# 11-Stimulation.net
KiCad netlist of a schematic drawn in Altium Designer
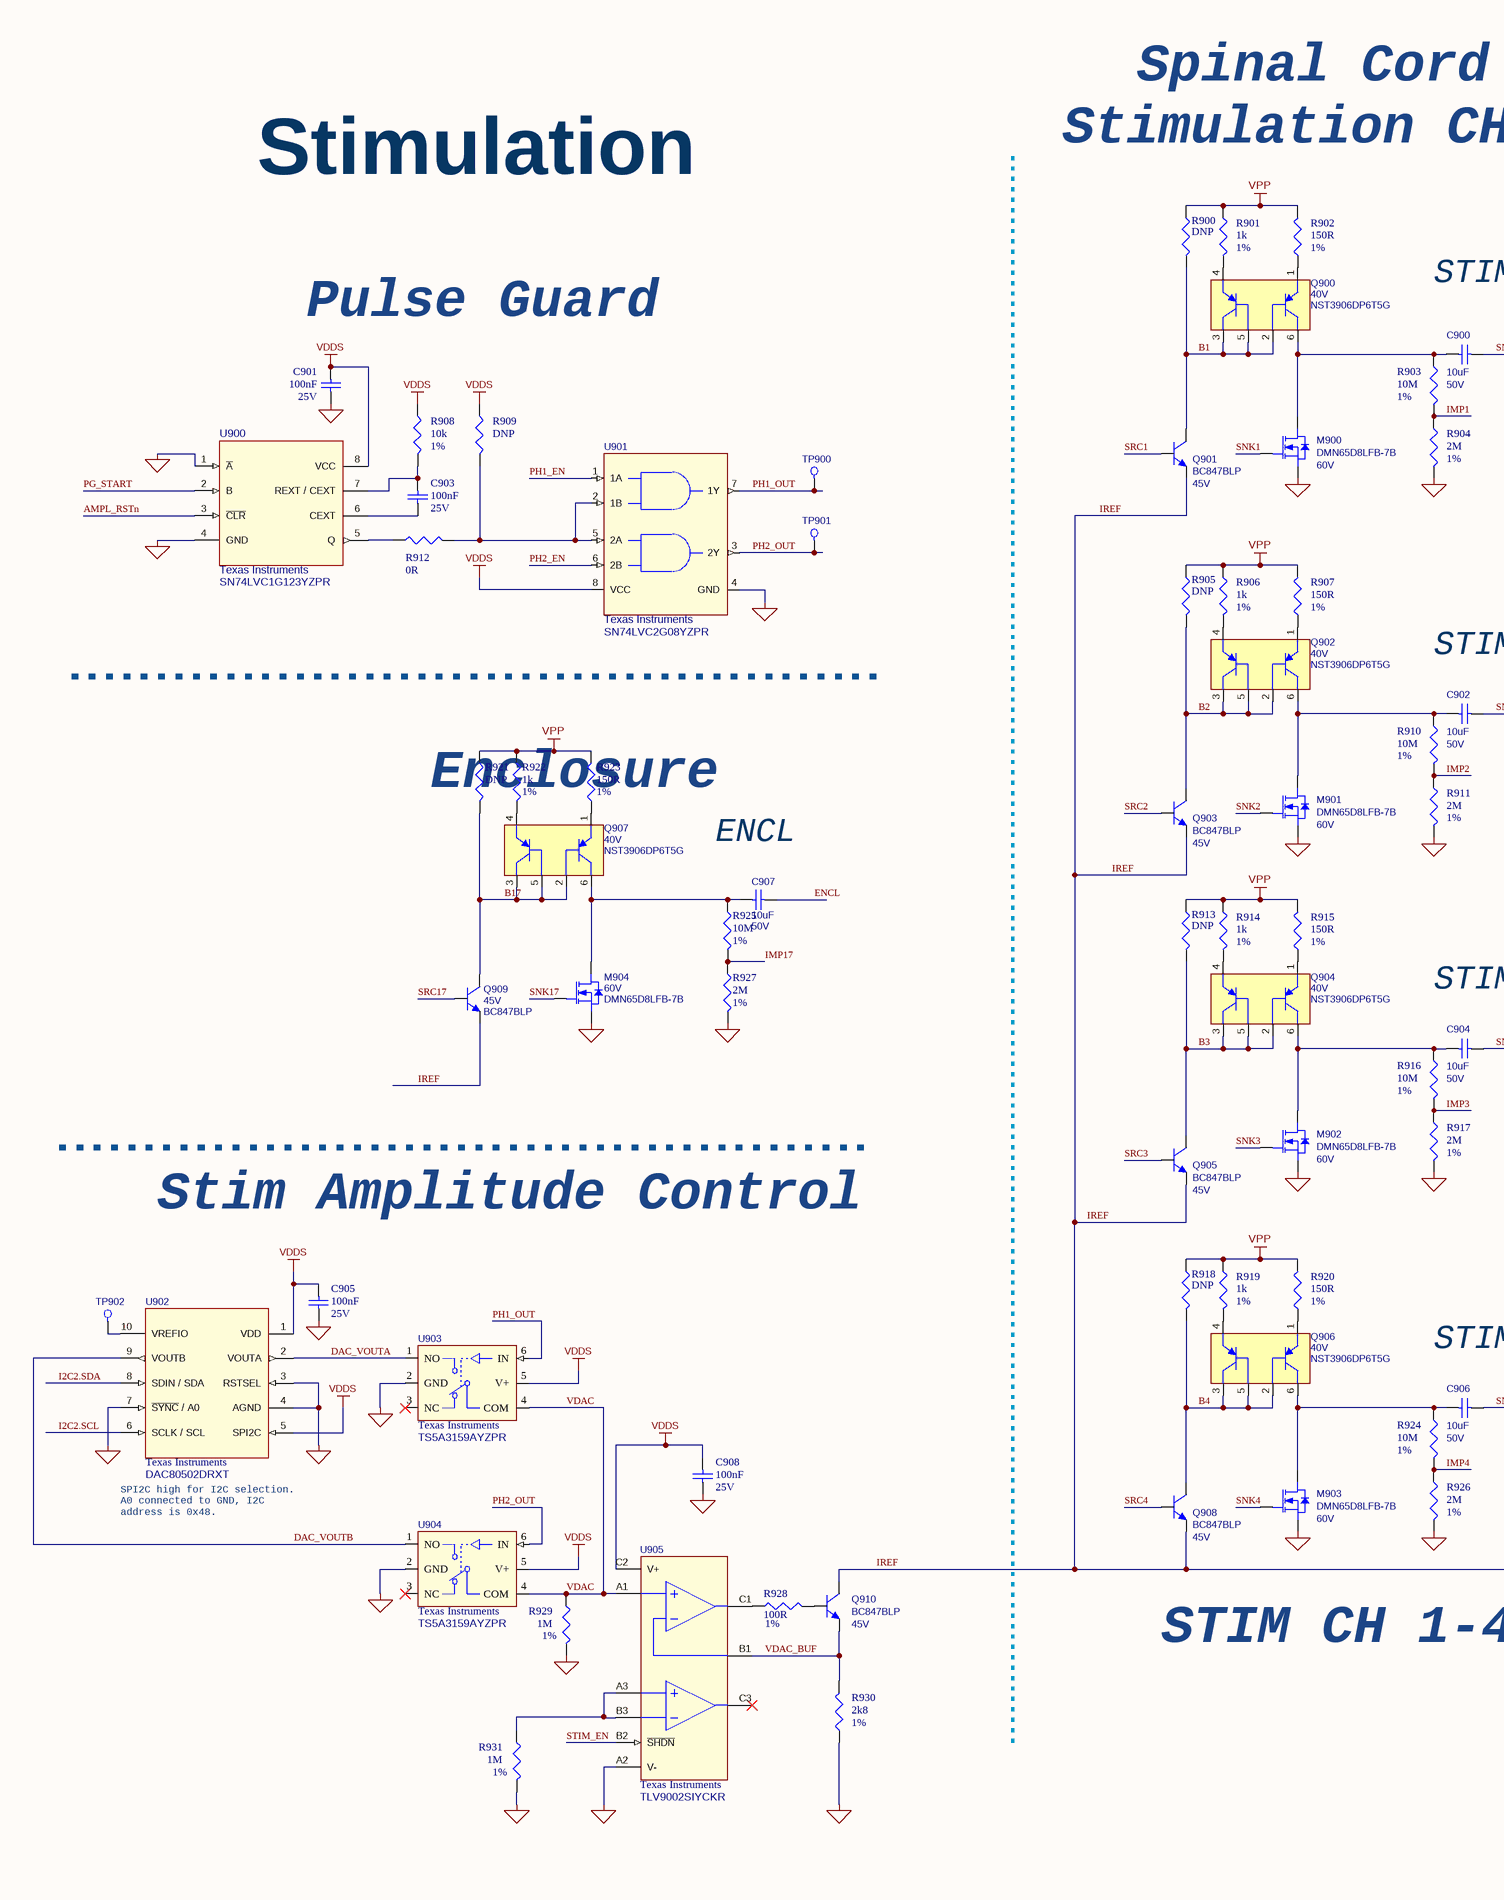
[diagram p0: 11-Stimulation.SchDoc, left]
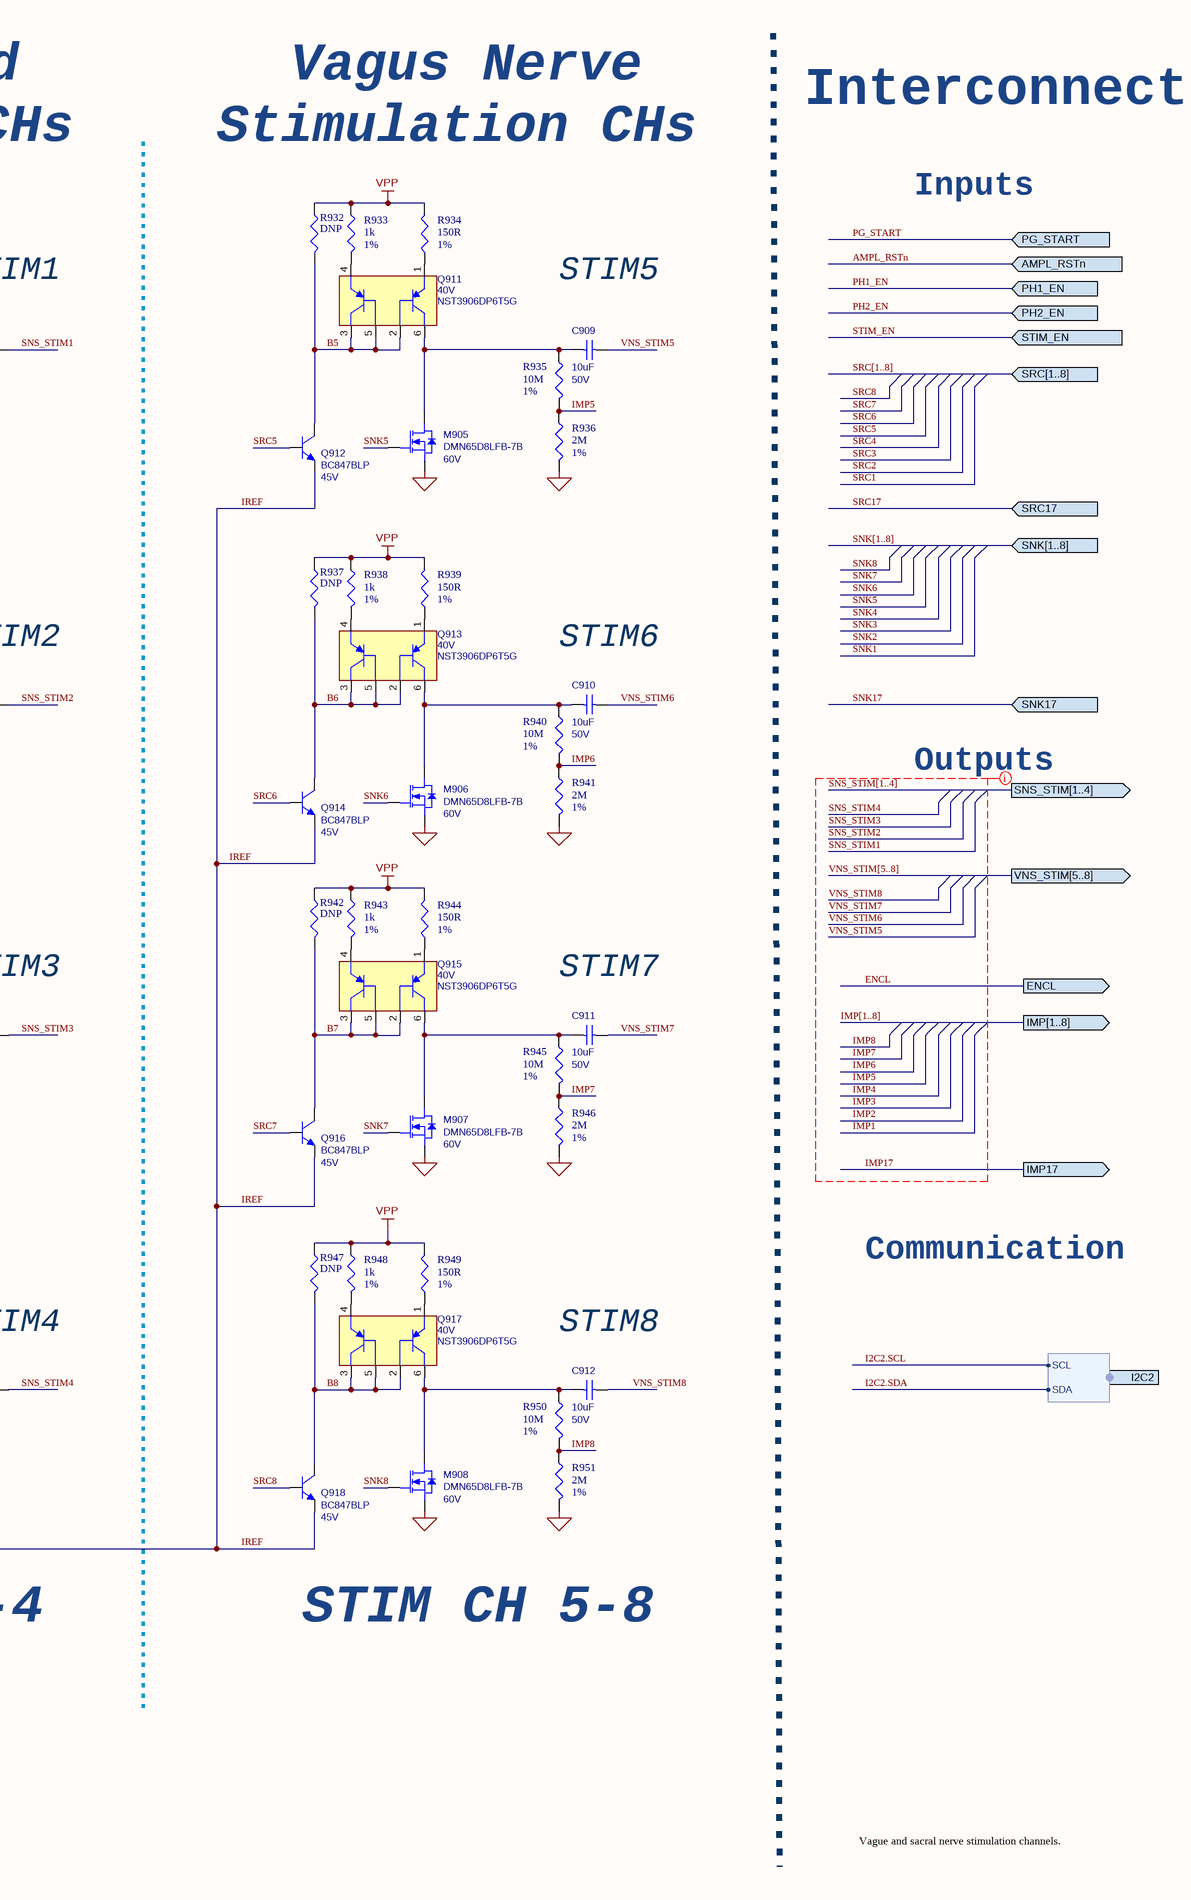
[diagram p1: 11-Stimulation.SchDoc, right]

(export (version "E")
  (design (tool "Eeschema 10.0.6"))
  (components
    (comp (ref "C900")
      (value "10uF")
      (footprint "CAP0805_REDUCED")
      (description "Capacitor, 10uF, X5R, 50V, 10%, 0805")
      (fields
        (field (name "MANUFACTURER") "Murata")
        (field (name "RATING") "50V")
        (field (name "MANUFACTURER PART NUMBER") "GRM21BR61H106ME43L")
      )
      (libsource (lib "MP-LIBRARY") (part "GRM21BR61H106ME43L"))
    )
    (comp (ref "C901")
      (value "100nF")
      (footprint "C0201_C")
      (fields
        (field (name "MANUFACTURER") "Murata")
        (field (name "MANUFACTURER PART NUMBER") "GRM033R61E104KE14J")
        (field (name "RATED DC VOLTAGE (URDC)") "25V")
      )
      (libsource (lib "MP-LIBRARY") (part "GRM033R61E104KE14J"))
    )
    (comp (ref "C902")
      (value "10uF")
      (footprint "CAP0805_REDUCED")
      (description "Capacitor, 10uF, X5R, 50V, 10%, 0805")
      (fields
        (field (name "MANUFACTURER") "Murata")
        (field (name "RATING") "50V")
        (field (name "MANUFACTURER PART NUMBER") "GRM21BR61H106ME43L")
      )
      (libsource (lib "MP-LIBRARY") (part "GRM21BR61H106ME43L"))
    )
    (comp (ref "C903")
      (value "100nF")
      (footprint "C0201_C")
      (fields
        (field (name "MANUFACTURER") "Murata")
        (field (name "MANUFACTURER PART NUMBER") "GRM033R61E104KE14J")
        (field (name "RATED DC VOLTAGE (URDC)") "25V")
      )
      (libsource (lib "MP-LIBRARY") (part "GRM033R61E104KE14J"))
    )
    (comp (ref "C904")
      (value "10uF")
      (footprint "CAP0805_REDUCED")
      (description "Capacitor, 10uF, X5R, 50V, 10%, 0805")
      (fields
        (field (name "MANUFACTURER") "Murata")
        (field (name "RATING") "50V")
        (field (name "MANUFACTURER PART NUMBER") "GRM21BR61H106ME43L")
      )
      (libsource (lib "MP-LIBRARY") (part "GRM21BR61H106ME43L"))
    )
    (comp (ref "C905")
      (value "100nF")
      (footprint "C0201_C")
      (fields
        (field (name "MANUFACTURER") "Murata")
        (field (name "MANUFACTURER PART NUMBER") "GRM033R61E104KE14J")
        (field (name "RATED DC VOLTAGE (URDC)") "25V")
      )
      (libsource (lib "MP-LIBRARY") (part "GRM033R61E104KE14J"))
    )
    (comp (ref "C906")
      (value "10uF")
      (footprint "CAP0805_REDUCED")
      (description "Capacitor, 10uF, X5R, 50V, 10%, 0805")
      (fields
        (field (name "MANUFACTURER") "Murata")
        (field (name "RATING") "50V")
        (field (name "MANUFACTURER PART NUMBER") "GRM21BR61H106ME43L")
      )
      (libsource (lib "MP-LIBRARY") (part "GRM21BR61H106ME43L"))
    )
    (comp (ref "C907")
      (value "10uF")
      (footprint "CAP0805_REDUCED")
      (description "Capacitor, 10uF, X5R, 50V, 10%, 0805")
      (fields
        (field (name "MANUFACTURER") "Murata")
        (field (name "RATING") "50V")
        (field (name "MANUFACTURER PART NUMBER") "GRM21BR61H106ME43L")
      )
      (libsource (lib "MP-LIBRARY") (part "GRM21BR61H106ME43L"))
    )
    (comp (ref "C908")
      (value "100nF")
      (footprint "C0201_C")
      (fields
        (field (name "MANUFACTURER") "Murata")
        (field (name "MANUFACTURER PART NUMBER") "GRM033R61E104KE14J")
        (field (name "RATED DC VOLTAGE (URDC)") "25V")
      )
      (libsource (lib "MP-LIBRARY") (part "GRM033R61E104KE14J"))
    )
    (comp (ref "C909")
      (value "10uF")
      (footprint "CAP0805_REDUCED")
      (description "Capacitor, 10uF, X5R, 50V, 10%, 0805")
      (fields
        (field (name "MANUFACTURER") "Murata")
        (field (name "RATING") "50V")
        (field (name "MANUFACTURER PART NUMBER") "GRM21BR61H106ME43L")
      )
      (libsource (lib "MP-LIBRARY") (part "GRM21BR61H106ME43L"))
    )
    (comp (ref "C910")
      (value "10uF")
      (footprint "CAP0805_REDUCED")
      (description "Capacitor, 10uF, X5R, 50V, 10%, 0805")
      (fields
        (field (name "MANUFACTURER") "Murata")
        (field (name "RATING") "50V")
        (field (name "MANUFACTURER PART NUMBER") "GRM21BR61H106ME43L")
      )
      (libsource (lib "MP-LIBRARY") (part "GRM21BR61H106ME43L"))
    )
    (comp (ref "C911")
      (value "10uF")
      (footprint "CAP0805_REDUCED")
      (description "Capacitor, 10uF, X5R, 50V, 10%, 0805")
      (fields
        (field (name "MANUFACTURER") "Murata")
        (field (name "RATING") "50V")
        (field (name "MANUFACTURER PART NUMBER") "GRM21BR61H106ME43L")
      )
      (libsource (lib "MP-LIBRARY") (part "GRM21BR61H106ME43L"))
    )
    (comp (ref "C912")
      (value "10uF")
      (footprint "CAP0805_REDUCED")
      (description "Capacitor, 10uF, X5R, 50V, 10%, 0805")
      (fields
        (field (name "MANUFACTURER") "Murata")
        (field (name "RATING") "50V")
        (field (name "MANUFACTURER PART NUMBER") "GRM21BR61H106ME43L")
      )
      (libsource (lib "MP-LIBRARY") (part "GRM21BR61H106ME43L"))
    )
    (comp (ref "M900")
      (value "DMN65D8LFB-7B")
      (footprint "DIODESINC_X1-DFN1006-3")
      (description "MOSFET, N-Chan, 60V, 210mA, DFN1006")
      (fields (field (name "MANUFACTURER") "Diodes Inc") (field (name "RATING") "60V"))
      (libsource (lib "MP-LIBRARY") (part "DMN65D8LFB-7B"))
    )
    (comp (ref "M901")
      (value "DMN65D8LFB-7B")
      (footprint "DIODESINC_X1-DFN1006-3")
      (description "MOSFET, N-Chan, 60V, 210mA, DFN1006")
      (fields (field (name "MANUFACTURER") "Diodes Inc") (field (name "RATING") "60V"))
      (libsource (lib "MP-LIBRARY") (part "DMN65D8LFB-7B"))
    )
    (comp (ref "M902")
      (value "DMN65D8LFB-7B")
      (footprint "DIODESINC_X1-DFN1006-3")
      (description "MOSFET, N-Chan, 60V, 210mA, DFN1006")
      (fields (field (name "MANUFACTURER") "Diodes Inc") (field (name "RATING") "60V"))
      (libsource (lib "MP-LIBRARY") (part "DMN65D8LFB-7B"))
    )
    (comp (ref "M903")
      (value "DMN65D8LFB-7B")
      (footprint "DIODESINC_X1-DFN1006-3")
      (description "MOSFET, N-Chan, 60V, 210mA, DFN1006")
      (fields (field (name "MANUFACTURER") "Diodes Inc") (field (name "RATING") "60V"))
      (libsource (lib "MP-LIBRARY") (part "DMN65D8LFB-7B"))
    )
    (comp (ref "M904")
      (value "DMN65D8LFB-7B")
      (footprint "DIODESINC_X1-DFN1006-3")
      (description "MOSFET, N-Chan, 60V, 210mA, DFN1006")
      (fields (field (name "MANUFACTURER") "Diodes Inc") (field (name "RATING") "60V"))
      (libsource (lib "MP-LIBRARY") (part "DMN65D8LFB-7B"))
    )
    (comp (ref "M905")
      (value "DMN65D8LFB-7B")
      (footprint "DIODESINC_X1-DFN1006-3")
      (description "MOSFET, N-Chan, 60V, 210mA, DFN1006")
      (fields (field (name "MANUFACTURER") "Diodes Inc") (field (name "RATING") "60V"))
      (libsource (lib "MP-LIBRARY") (part "DMN65D8LFB-7B"))
    )
    (comp (ref "M906")
      (value "DMN65D8LFB-7B")
      (footprint "DIODESINC_X1-DFN1006-3")
      (description "MOSFET, N-Chan, 60V, 210mA, DFN1006")
      (fields (field (name "MANUFACTURER") "Diodes Inc") (field (name "RATING") "60V"))
      (libsource (lib "MP-LIBRARY") (part "DMN65D8LFB-7B"))
    )
    (comp (ref "M907")
      (value "DMN65D8LFB-7B")
      (footprint "DIODESINC_X1-DFN1006-3")
      (description "MOSFET, N-Chan, 60V, 210mA, DFN1006")
      (fields (field (name "MANUFACTURER") "Diodes Inc") (field (name "RATING") "60V"))
      (libsource (lib "MP-LIBRARY") (part "DMN65D8LFB-7B"))
    )
    (comp (ref "M908")
      (value "DMN65D8LFB-7B")
      (footprint "DIODESINC_X1-DFN1006-3")
      (description "MOSFET, N-Chan, 60V, 210mA, DFN1006")
      (fields (field (name "MANUFACTURER") "Diodes Inc") (field (name "RATING") "60V"))
      (libsource (lib "MP-LIBRARY") (part "DMN65D8LFB-7B"))
    )
    (comp (ref "Q900")
      (value "NST3906DP6T5G")
      (footprint "DIODESINC_SOT-963-6")
      (description "TRANS 2PNP 40V 0.2A SOT963")
      (fields (field (name "MANUFACTURER") "ON Semi") (field (name "RATING") "40V"))
      (libsource (lib "MP-LIBRARY") (part "NST3906DP6T5G"))
    )
    (comp (ref "Q901")
      (value "BC847BLP")
      (footprint "DIODESINC_X1-DFN1006-3")
      (description "Transistor, NPN, 45V, 100mA, DFN1006")
      (fields
        (field (name "MANUFACTURER") "Diodes Inc")
        (field (name "RATING") "45V")
        (field (name "MANUFACTURER PART NUMBER") "BC847BLP-7B")
      )
      (libsource (lib "MP-LIBRARY") (part "BC847BLP-7B"))
    )
    (comp (ref "Q902")
      (value "NST3906DP6T5G")
      (footprint "DIODESINC_SOT-963-6")
      (description "TRANS 2PNP 40V 0.2A SOT963")
      (fields (field (name "MANUFACTURER") "ON Semi") (field (name "RATING") "40V"))
      (libsource (lib "MP-LIBRARY") (part "NST3906DP6T5G"))
    )
    (comp (ref "Q903")
      (value "BC847BLP")
      (footprint "DIODESINC_X1-DFN1006-3")
      (description "Transistor, NPN, 45V, 100mA, DFN1006")
      (fields
        (field (name "MANUFACTURER") "Diodes Inc")
        (field (name "RATING") "45V")
        (field (name "MANUFACTURER PART NUMBER") "BC847BLP-7B")
      )
      (libsource (lib "MP-LIBRARY") (part "BC847BLP-7B"))
    )
    (comp (ref "Q904")
      (value "NST3906DP6T5G")
      (footprint "DIODESINC_SOT-963-6")
      (description "TRANS 2PNP 40V 0.2A SOT963")
      (fields (field (name "MANUFACTURER") "ON Semi") (field (name "RATING") "40V"))
      (libsource (lib "MP-LIBRARY") (part "NST3906DP6T5G"))
    )
    (comp (ref "Q905")
      (value "BC847BLP")
      (footprint "DIODESINC_X1-DFN1006-3")
      (description "Transistor, NPN, 45V, 100mA, DFN1006")
      (fields
        (field (name "MANUFACTURER") "Diodes Inc")
        (field (name "RATING") "45V")
        (field (name "MANUFACTURER PART NUMBER") "BC847BLP-7B")
      )
      (libsource (lib "MP-LIBRARY") (part "BC847BLP-7B"))
    )
    (comp (ref "Q906")
      (value "NST3906DP6T5G")
      (footprint "DIODESINC_SOT-963-6")
      (description "TRANS 2PNP 40V 0.2A SOT963")
      (fields (field (name "MANUFACTURER") "ON Semi") (field (name "RATING") "40V"))
      (libsource (lib "MP-LIBRARY") (part "NST3906DP6T5G"))
    )
    (comp (ref "Q907")
      (value "NST3906DP6T5G")
      (footprint "DIODESINC_SOT-963-6")
      (description "TRANS 2PNP 40V 0.2A SOT963")
      (fields (field (name "MANUFACTURER") "ON Semi") (field (name "RATING") "40V"))
      (libsource (lib "MP-LIBRARY") (part "NST3906DP6T5G"))
    )
    (comp (ref "Q908")
      (value "BC847BLP")
      (footprint "DIODESINC_X1-DFN1006-3")
      (description "Transistor, NPN, 45V, 100mA, DFN1006")
      (fields
        (field (name "MANUFACTURER") "Diodes Inc")
        (field (name "RATING") "45V")
        (field (name "MANUFACTURER PART NUMBER") "BC847BLP-7B")
      )
      (libsource (lib "MP-LIBRARY") (part "BC847BLP-7B"))
    )
    (comp (ref "Q909")
      (value "BC847BLP")
      (footprint "DIODESINC_X1-DFN1006-3")
      (description "Transistor, NPN, 45V, 100mA, DFN1006")
      (fields
        (field (name "MANUFACTURER") "Diodes Inc")
        (field (name "RATING") "45V")
        (field (name "MANUFACTURER PART NUMBER") "BC847BLP-7B")
      )
      (libsource (lib "MP-LIBRARY") (part "BC847BLP-7B"))
    )
    (comp (ref "Q910")
      (value "BC847BLP")
      (footprint "DIODESINC_X1-DFN1006-3")
      (description "Transistor, NPN, 45V, 100mA, DFN1006")
      (fields
        (field (name "MANUFACTURER") "Diodes Inc")
        (field (name "RATING") "45V")
        (field (name "MANUFACTURER PART NUMBER") "BC847BLP-7B")
      )
      (libsource (lib "MP-LIBRARY") (part "BC847BLP-7B"))
    )
    (comp (ref "Q911")
      (value "NST3906DP6T5G")
      (footprint "DIODESINC_SOT-963-6")
      (description "TRANS 2PNP 40V 0.2A SOT963")
      (fields (field (name "MANUFACTURER") "ON Semi") (field (name "RATING") "40V"))
      (libsource (lib "MP-LIBRARY") (part "NST3906DP6T5G"))
    )
    (comp (ref "Q912")
      (value "BC847BLP")
      (footprint "DIODESINC_X1-DFN1006-3")
      (description "Transistor, NPN, 45V, 100mA, DFN1006")
      (fields
        (field (name "MANUFACTURER") "Diodes Inc")
        (field (name "RATING") "45V")
        (field (name "MANUFACTURER PART NUMBER") "BC847BLP-7B")
      )
      (libsource (lib "MP-LIBRARY") (part "BC847BLP-7B"))
    )
    (comp (ref "Q913")
      (value "NST3906DP6T5G")
      (footprint "DIODESINC_SOT-963-6")
      (description "TRANS 2PNP 40V 0.2A SOT963")
      (fields (field (name "MANUFACTURER") "ON Semi") (field (name "RATING") "40V"))
      (libsource (lib "MP-LIBRARY") (part "NST3906DP6T5G"))
    )
    (comp (ref "Q914")
      (value "BC847BLP")
      (footprint "DIODESINC_X1-DFN1006-3")
      (description "Transistor, NPN, 45V, 100mA, DFN1006")
      (fields
        (field (name "MANUFACTURER") "Diodes Inc")
        (field (name "RATING") "45V")
        (field (name "MANUFACTURER PART NUMBER") "BC847BLP-7B")
      )
      (libsource (lib "MP-LIBRARY") (part "BC847BLP-7B"))
    )
    (comp (ref "Q915")
      (value "NST3906DP6T5G")
      (footprint "DIODESINC_SOT-963-6")
      (description "TRANS 2PNP 40V 0.2A SOT963")
      (fields (field (name "MANUFACTURER") "ON Semi") (field (name "RATING") "40V"))
      (libsource (lib "MP-LIBRARY") (part "NST3906DP6T5G"))
    )
    (comp (ref "Q916")
      (value "BC847BLP")
      (footprint "DIODESINC_X1-DFN1006-3")
      (description "Transistor, NPN, 45V, 100mA, DFN1006")
      (fields
        (field (name "MANUFACTURER") "Diodes Inc")
        (field (name "RATING") "45V")
        (field (name "MANUFACTURER PART NUMBER") "BC847BLP-7B")
      )
      (libsource (lib "MP-LIBRARY") (part "BC847BLP-7B"))
    )
    (comp (ref "Q917")
      (value "NST3906DP6T5G")
      (footprint "DIODESINC_SOT-963-6")
      (description "TRANS 2PNP 40V 0.2A SOT963")
      (fields (field (name "MANUFACTURER") "ON Semi") (field (name "RATING") "40V"))
      (libsource (lib "MP-LIBRARY") (part "NST3906DP6T5G"))
    )
    (comp (ref "Q918")
      (value "BC847BLP")
      (footprint "DIODESINC_X1-DFN1006-3")
      (description "Transistor, NPN, 45V, 100mA, DFN1006")
      (fields
        (field (name "MANUFACTURER") "Diodes Inc")
        (field (name "RATING") "45V")
        (field (name "MANUFACTURER PART NUMBER") "BC847BLP-7B")
      )
      (libsource (lib "MP-LIBRARY") (part "BC847BLP-7B"))
    )
    (comp (ref "R900")
      (value "DNP")
      (footprint "R0201_C")
      (fields (field (name "Comment") "RES_DNP_0201"))
      (libsource (lib "MP-LIBRARY") (part "RES_DNP_0201"))
    )
    (comp (ref "R901")
      (value "1k")
      (footprint "R0201_C")
      (fields
        (field (name "MANUFACTURER") "Vishay")
        (field (name "MANUFACTURER PART NUMBER") "CRCW02011K00FNED")
        (field (name "TOLERANCE") "1%")
        (field (name "POWER") "50mW")
      )
      (libsource (lib "MP-LIBRARY") (part "CRCW02011K00FNED"))
    )
    (comp (ref "R902")
      (value "150R")
      (footprint "R0201_C")
      (fields
        (field (name "MANUFACTURER") "Vishay")
        (field (name "MANUFACTURER PART NUMBER") "CRCW0201150RFNED")
        (field (name "TOLERANCE") "1%")
        (field (name "POWER") "50mW")
      )
      (libsource (lib "MP-LIBRARY") (part "CRCW0201150RFNED"))
    )
    (comp (ref "R903")
      (value "10M")
      (footprint "R0201_C")
      (fields
        (field (name "MANUFACTURER") "Vishay Draloric")
        (field (name "MANUFACTURER PART NUMBER") "CRCW020110M0FNED")
        (field (name "TOLERANCE") "1%")
        (field (name "POWER") "50mW")
      )
      (libsource (lib "MP-LIBRARY") (part "CRCW020110M0FNED"))
    )
    (comp (ref "R904")
      (value "2M")
      (footprint "R0201_C")
      (fields
        (field (name "MANUFACTURER") "Vishay Draloric")
        (field (name "MANUFACTURER PART NUMBER") "CRCW02012M00FNED")
        (field (name "TOLERANCE") "1%")
        (field (name "POWER") "50mW")
      )
      (libsource (lib "MP-LIBRARY") (part "CRCW02012M00FNED"))
    )
    (comp (ref "R905")
      (value "DNP")
      (footprint "R0201_C")
      (fields (field (name "Comment") "RES_DNP_0201"))
      (libsource (lib "MP-LIBRARY") (part "RES_DNP_0201"))
    )
    (comp (ref "R906")
      (value "1k")
      (footprint "R0201_C")
      (fields
        (field (name "MANUFACTURER") "Vishay")
        (field (name "MANUFACTURER PART NUMBER") "CRCW02011K00FNED")
        (field (name "TOLERANCE") "1%")
        (field (name "POWER") "50mW")
      )
      (libsource (lib "MP-LIBRARY") (part "CRCW02011K00FNED"))
    )
    (comp (ref "R907")
      (value "150R")
      (footprint "R0201_C")
      (fields
        (field (name "MANUFACTURER") "Vishay")
        (field (name "MANUFACTURER PART NUMBER") "CRCW0201150RFNED")
        (field (name "TOLERANCE") "1%")
        (field (name "POWER") "50mW")
      )
      (libsource (lib "MP-LIBRARY") (part "CRCW0201150RFNED"))
    )
    (comp (ref "R908")
      (value "10k")
      (footprint "R0201_C")
      (fields
        (field (name "MANUFACTURER") "Vishay")
        (field (name "MANUFACTURER PART NUMBER") "CRCW020110K0FNED")
        (field (name "TOLERANCE") "1%")
        (field (name "POWER") "50mW")
      )
      (libsource (lib "MP-LIBRARY") (part "CRCW020110K0FNED"))
    )
    (comp (ref "R909")
      (value "DNP")
      (footprint "R0201_C")
      (fields (field (name "Comment") "RES_DNP_0201"))
      (libsource (lib "MP-LIBRARY") (part "RES_DNP_0201"))
    )
    (comp (ref "R910")
      (value "10M")
      (footprint "R0201_C")
      (fields
        (field (name "MANUFACTURER") "Vishay Draloric")
        (field (name "MANUFACTURER PART NUMBER") "CRCW020110M0FNED")
        (field (name "TOLERANCE") "1%")
        (field (name "POWER") "50mW")
      )
      (libsource (lib "MP-LIBRARY") (part "CRCW020110M0FNED"))
    )
    (comp (ref "R911")
      (value "2M")
      (footprint "R0201_C")
      (fields
        (field (name "MANUFACTURER") "Vishay Draloric")
        (field (name "MANUFACTURER PART NUMBER") "CRCW02012M00FNED")
        (field (name "TOLERANCE") "1%")
        (field (name "POWER") "50mW")
      )
      (libsource (lib "MP-LIBRARY") (part "CRCW02012M00FNED"))
    )
    (comp (ref "R912")
      (value "0R")
      (footprint "R0201_C")
      (description "Fixed Resistor, Metal Glaze/thick Film, 0.05W, 0ohm, Surface Mount, 0201")
      (fields
        (field (name "MANUFACTURER") "Vishay")
        (field (name "MANUFACTURER PART NUMBER") "CRCW02010000Z0ED")
      )
      (libsource (lib "MP-LIBRARY") (part "CRCW02010000Z0ED"))
    )
    (comp (ref "R913")
      (value "DNP")
      (footprint "R0201_C")
      (fields (field (name "Comment") "RES_DNP_0201"))
      (libsource (lib "MP-LIBRARY") (part "RES_DNP_0201"))
    )
    (comp (ref "R914")
      (value "1k")
      (footprint "R0201_C")
      (fields
        (field (name "MANUFACTURER") "Vishay")
        (field (name "MANUFACTURER PART NUMBER") "CRCW02011K00FNED")
        (field (name "TOLERANCE") "1%")
        (field (name "POWER") "50mW")
      )
      (libsource (lib "MP-LIBRARY") (part "CRCW02011K00FNED"))
    )
    (comp (ref "R915")
      (value "150R")
      (footprint "R0201_C")
      (fields
        (field (name "MANUFACTURER") "Vishay")
        (field (name "MANUFACTURER PART NUMBER") "CRCW0201150RFNED")
        (field (name "TOLERANCE") "1%")
        (field (name "POWER") "50mW")
      )
      (libsource (lib "MP-LIBRARY") (part "CRCW0201150RFNED"))
    )
    (comp (ref "R916")
      (value "10M")
      (footprint "R0201_C")
      (fields
        (field (name "MANUFACTURER") "Vishay Draloric")
        (field (name "MANUFACTURER PART NUMBER") "CRCW020110M0FNED")
        (field (name "TOLERANCE") "1%")
        (field (name "POWER") "50mW")
      )
      (libsource (lib "MP-LIBRARY") (part "CRCW020110M0FNED"))
    )
    (comp (ref "R917")
      (value "2M")
      (footprint "R0201_C")
      (fields
        (field (name "MANUFACTURER") "Vishay Draloric")
        (field (name "MANUFACTURER PART NUMBER") "CRCW02012M00FNED")
        (field (name "TOLERANCE") "1%")
        (field (name "POWER") "50mW")
      )
      (libsource (lib "MP-LIBRARY") (part "CRCW02012M00FNED"))
    )
    (comp (ref "R918")
      (value "DNP")
      (footprint "R0201_C")
      (fields (field (name "Comment") "RES_DNP_0201"))
      (libsource (lib "MP-LIBRARY") (part "RES_DNP_0201"))
    )
    (comp (ref "R919")
      (value "1k")
      (footprint "R0201_C")
      (fields
        (field (name "MANUFACTURER") "Vishay")
        (field (name "MANUFACTURER PART NUMBER") "CRCW02011K00FNED")
        (field (name "TOLERANCE") "1%")
        (field (name "POWER") "50mW")
      )
      (libsource (lib "MP-LIBRARY") (part "CRCW02011K00FNED"))
    )
    (comp (ref "R920")
      (value "150R")
      (footprint "R0201_C")
      (fields
        (field (name "MANUFACTURER") "Vishay")
        (field (name "MANUFACTURER PART NUMBER") "CRCW0201150RFNED")
        (field (name "TOLERANCE") "1%")
        (field (name "POWER") "50mW")
      )
      (libsource (lib "MP-LIBRARY") (part "CRCW0201150RFNED"))
    )
    (comp (ref "R921")
      (value "DNP")
      (footprint "R0201_C")
      (fields (field (name "Comment") "RES_DNP_0201"))
      (libsource (lib "MP-LIBRARY") (part "RES_DNP_0201"))
    )
    (comp (ref "R922")
      (value "1k")
      (footprint "R0201_C")
      (fields
        (field (name "MANUFACTURER") "Vishay")
        (field (name "MANUFACTURER PART NUMBER") "CRCW02011K00FNED")
        (field (name "TOLERANCE") "1%")
        (field (name "POWER") "50mW")
      )
      (libsource (lib "MP-LIBRARY") (part "CRCW02011K00FNED"))
    )
    (comp (ref "R923")
      (value "150R")
      (footprint "R0201_C")
      (fields
        (field (name "MANUFACTURER") "Vishay")
        (field (name "MANUFACTURER PART NUMBER") "CRCW0201150RFNED")
        (field (name "TOLERANCE") "1%")
        (field (name "POWER") "50mW")
      )
      (libsource (lib "MP-LIBRARY") (part "CRCW0201150RFNED"))
    )
    (comp (ref "R924")
      (value "10M")
      (footprint "R0201_C")
      (fields
        (field (name "MANUFACTURER") "Vishay Draloric")
        (field (name "MANUFACTURER PART NUMBER") "CRCW020110M0FNED")
        (field (name "TOLERANCE") "1%")
        (field (name "POWER") "50mW")
      )
      (libsource (lib "MP-LIBRARY") (part "CRCW020110M0FNED"))
    )
    (comp (ref "R925")
      (value "10M")
      (footprint "R0201_C")
      (fields
        (field (name "MANUFACTURER") "Vishay Draloric")
        (field (name "MANUFACTURER PART NUMBER") "CRCW020110M0FNED")
        (field (name "TOLERANCE") "1%")
        (field (name "POWER") "50mW")
      )
      (libsource (lib "MP-LIBRARY") (part "CRCW020110M0FNED"))
    )
    (comp (ref "R926")
      (value "2M")
      (footprint "R0201_C")
      (fields
        (field (name "MANUFACTURER") "Vishay Draloric")
        (field (name "MANUFACTURER PART NUMBER") "CRCW02012M00FNED")
        (field (name "TOLERANCE") "1%")
        (field (name "POWER") "50mW")
      )
      (libsource (lib "MP-LIBRARY") (part "CRCW02012M00FNED"))
    )
    (comp (ref "R927")
      (value "2M")
      (footprint "R0201_C")
      (fields
        (field (name "MANUFACTURER") "Vishay Draloric")
        (field (name "MANUFACTURER PART NUMBER") "CRCW02012M00FNED")
        (field (name "TOLERANCE") "1%")
        (field (name "POWER") "50mW")
      )
      (libsource (lib "MP-LIBRARY") (part "CRCW02012M00FNED"))
    )
    (comp (ref "R928")
      (value "100R")
      (footprint "R0201_C")
      (fields
        (field (name "MANUFACTURER") "Vishay")
        (field (name "MANUFACTURER PART NUMBER") "CRCW0201100RFNED")
        (field (name "TOLERANCE") "1%")
        (field (name "POWER") "50mW")
      )
      (libsource (lib "MP-LIBRARY") (part "CRCW0201100RFNED"))
    )
    (comp (ref "R929")
      (value "1M")
      (footprint "R0201_C")
      (fields
        (field (name "MANUFACTURER") "Vishay")
        (field (name "MANUFACTURER PART NUMBER") "CRCW02011M00FNED")
        (field (name "TOLERANCE") "1%")
        (field (name "POWER") "50mW")
      )
      (libsource (lib "MP-LIBRARY") (part "CRCW02011M00FNED"))
    )
    (comp (ref "R930")
      (value "2k8")
      (footprint "R0201_C")
      (fields
        (field (name "MANUFACTURER") "Vishay")
        (field (name "MANUFACTURER PART NUMBER") "CRCW02012K80FNED")
        (field (name "TOLERANCE") "1%")
        (field (name "POWER") "50mW")
      )
      (libsource (lib "MP-LIBRARY") (part "CRCW02012K80FNED"))
    )
    (comp (ref "R931")
      (value "1M")
      (footprint "R0201_C")
      (fields
        (field (name "MANUFACTURER") "Vishay")
        (field (name "MANUFACTURER PART NUMBER") "CRCW02011M00FNED")
        (field (name "TOLERANCE") "1%")
        (field (name "POWER") "50mW")
      )
      (libsource (lib "MP-LIBRARY") (part "CRCW02011M00FNED"))
    )
    (comp (ref "R932")
      (value "DNP")
      (footprint "R0201_C")
      (fields (field (name "Comment") "RES_DNP_0201"))
      (libsource (lib "MP-LIBRARY") (part "RES_DNP_0201"))
    )
    (comp (ref "R933")
      (value "1k")
      (footprint "R0201_C")
      (fields
        (field (name "MANUFACTURER") "Vishay")
        (field (name "MANUFACTURER PART NUMBER") "CRCW02011K00FNED")
        (field (name "TOLERANCE") "1%")
        (field (name "POWER") "50mW")
      )
      (libsource (lib "MP-LIBRARY") (part "CRCW02011K00FNED"))
    )
    (comp (ref "R934")
      (value "150R")
      (footprint "R0201_C")
      (fields
        (field (name "MANUFACTURER") "Vishay")
        (field (name "MANUFACTURER PART NUMBER") "CRCW0201150RFNED")
        (field (name "TOLERANCE") "1%")
        (field (name "POWER") "50mW")
      )
      (libsource (lib "MP-LIBRARY") (part "CRCW0201150RFNED"))
    )
    (comp (ref "R935")
      (value "10M")
      (footprint "R0201_C")
      (fields
        (field (name "MANUFACTURER") "Vishay Draloric")
        (field (name "MANUFACTURER PART NUMBER") "CRCW020110M0FNED")
        (field (name "TOLERANCE") "1%")
        (field (name "POWER") "50mW")
      )
      (libsource (lib "MP-LIBRARY") (part "CRCW020110M0FNED"))
    )
    (comp (ref "R936")
      (value "2M")
      (footprint "R0201_C")
      (fields
        (field (name "MANUFACTURER") "Vishay Draloric")
        (field (name "MANUFACTURER PART NUMBER") "CRCW02012M00FNED")
        (field (name "TOLERANCE") "1%")
        (field (name "POWER") "50mW")
      )
      (libsource (lib "MP-LIBRARY") (part "CRCW02012M00FNED"))
    )
    (comp (ref "R937")
      (value "DNP")
      (footprint "R0201_C")
      (fields (field (name "Comment") "RES_DNP_0201"))
      (libsource (lib "MP-LIBRARY") (part "RES_DNP_0201"))
    )
    (comp (ref "R938")
      (value "1k")
      (footprint "R0201_C")
      (fields
        (field (name "MANUFACTURER") "Vishay")
        (field (name "MANUFACTURER PART NUMBER") "CRCW02011K00FNED")
        (field (name "TOLERANCE") "1%")
        (field (name "POWER") "50mW")
      )
      (libsource (lib "MP-LIBRARY") (part "CRCW02011K00FNED"))
    )
    (comp (ref "R939")
      (value "150R")
      (footprint "R0201_C")
      (fields
        (field (name "MANUFACTURER") "Vishay")
        (field (name "MANUFACTURER PART NUMBER") "CRCW0201150RFNED")
        (field (name "TOLERANCE") "1%")
        (field (name "POWER") "50mW")
      )
      (libsource (lib "MP-LIBRARY") (part "CRCW0201150RFNED"))
    )
    (comp (ref "R940")
      (value "10M")
      (footprint "R0201_C")
      (fields
        (field (name "MANUFACTURER") "Vishay Draloric")
        (field (name "MANUFACTURER PART NUMBER") "CRCW020110M0FNED")
        (field (name "TOLERANCE") "1%")
        (field (name "POWER") "50mW")
      )
      (libsource (lib "MP-LIBRARY") (part "CRCW020110M0FNED"))
    )
    (comp (ref "R941")
      (value "2M")
      (footprint "R0201_C")
      (fields
        (field (name "MANUFACTURER") "Vishay Draloric")
        (field (name "MANUFACTURER PART NUMBER") "CRCW02012M00FNED")
        (field (name "TOLERANCE") "1%")
        (field (name "POWER") "50mW")
      )
      (libsource (lib "MP-LIBRARY") (part "CRCW02012M00FNED"))
    )
    (comp (ref "R942")
      (value "DNP")
      (footprint "R0201_C")
      (fields (field (name "Comment") "RES_DNP_0201"))
      (libsource (lib "MP-LIBRARY") (part "RES_DNP_0201"))
    )
    (comp (ref "R943")
      (value "1k")
      (footprint "R0201_C")
      (fields
        (field (name "MANUFACTURER") "Vishay")
        (field (name "MANUFACTURER PART NUMBER") "CRCW02011K00FNED")
        (field (name "TOLERANCE") "1%")
        (field (name "POWER") "50mW")
      )
      (libsource (lib "MP-LIBRARY") (part "CRCW02011K00FNED"))
    )
    (comp (ref "R944")
      (value "150R")
      (footprint "R0201_C")
      (fields
        (field (name "MANUFACTURER") "Vishay")
        (field (name "MANUFACTURER PART NUMBER") "CRCW0201150RFNED")
        (field (name "TOLERANCE") "1%")
        (field (name "POWER") "50mW")
      )
      (libsource (lib "MP-LIBRARY") (part "CRCW0201150RFNED"))
    )
    (comp (ref "R945")
      (value "10M")
      (footprint "R0201_C")
      (fields
        (field (name "MANUFACTURER") "Vishay Draloric")
        (field (name "MANUFACTURER PART NUMBER") "CRCW020110M0FNED")
        (field (name "TOLERANCE") "1%")
        (field (name "POWER") "50mW")
      )
      (libsource (lib "MP-LIBRARY") (part "CRCW020110M0FNED"))
    )
    (comp (ref "R946")
      (value "2M")
      (footprint "R0201_C")
      (fields
        (field (name "MANUFACTURER") "Vishay Draloric")
        (field (name "MANUFACTURER PART NUMBER") "CRCW02012M00FNED")
        (field (name "TOLERANCE") "1%")
        (field (name "POWER") "50mW")
      )
      (libsource (lib "MP-LIBRARY") (part "CRCW02012M00FNED"))
    )
    (comp (ref "R947")
      (value "DNP")
      (footprint "R0201_C")
      (fields (field (name "Comment") "RES_DNP_0201"))
      (libsource (lib "MP-LIBRARY") (part "RES_DNP_0201"))
    )
    (comp (ref "R948")
      (value "1k")
      (footprint "R0201_C")
      (fields
        (field (name "MANUFACTURER") "Vishay")
        (field (name "MANUFACTURER PART NUMBER") "CRCW02011K00FNED")
        (field (name "TOLERANCE") "1%")
        (field (name "POWER") "50mW")
      )
      (libsource (lib "MP-LIBRARY") (part "CRCW02011K00FNED"))
    )
    (comp (ref "R949")
      (value "150R")
      (footprint "R0201_C")
      (fields
        (field (name "MANUFACTURER") "Vishay")
        (field (name "MANUFACTURER PART NUMBER") "CRCW0201150RFNED")
        (field (name "TOLERANCE") "1%")
        (field (name "POWER") "50mW")
      )
      (libsource (lib "MP-LIBRARY") (part "CRCW0201150RFNED"))
    )
    (comp (ref "R950")
      (value "10M")
      (footprint "R0201_C")
      (fields
        (field (name "MANUFACTURER") "Vishay Draloric")
        (field (name "MANUFACTURER PART NUMBER") "CRCW020110M0FNED")
        (field (name "TOLERANCE") "1%")
        (field (name "POWER") "50mW")
      )
      (libsource (lib "MP-LIBRARY") (part "CRCW020110M0FNED"))
    )
    (comp (ref "R951")
      (value "2M")
      (footprint "R0201_C")
      (fields
        (field (name "MANUFACTURER") "Vishay Draloric")
        (field (name "MANUFACTURER PART NUMBER") "CRCW02012M00FNED")
        (field (name "TOLERANCE") "1%")
        (field (name "POWER") "50mW")
      )
      (libsource (lib "MP-LIBRARY") (part "CRCW02012M00FNED"))
    )
    (comp (ref "TP900")
      (value "Test Point")
      (footprint "testpad_0.9mm")
      (description "Test pad, 0.90mm circular pad")
      (libsource (lib "MP-LIBRARY") (part "Test Point"))
    )
    (comp (ref "TP901")
      (value "Test Point")
      (footprint "testpad_0.9mm")
      (description "Test pad, 0.90mm circular pad")
      (libsource (lib "MP-LIBRARY") (part "Test Point"))
    )
    (comp (ref "TP902")
      (value "Test Point")
      (footprint "testpad_0.9mm")
      (description "Test pad, 0.90mm circular pad")
      (libsource (lib "MP-LIBRARY") (part "Test Point"))
    )
    (comp (ref "U900")
      (value "SN74LVC1G123YZPR")
      (footprint "TI_YZP0008")
      (description "Monostable, RC set, dual triggers, BGA-8")
      (fields (field (name "MANUFACTURER") "Texas Instruments"))
      (libsource (lib "MP-LIBRARY") (part "SN74LVC1G123YZPR"))
    )
    (comp (ref "U901")
      (value "SN74LVC2G08YZPR")
      (footprint "TI_YZP0008")
      (description "AND gate, Dual 2-input, BGA-8")
      (fields (field (name "MANUFACTURER") "Texas Instruments"))
      (libsource (lib "MP-LIBRARY") (part "SN74LVC2G08YZPR"))
    )
    (comp (ref "U902")
      (value "DAC80502DRXT")
      (footprint "TI_DRX0010A")
      (description "DAC, 16-bit, Dual channel, SPI/I2C, WSON-10")
      (fields (field (name "MANUFACTURER") "Texas Instruments"))
      (libsource (lib "MP-LIBRARY") (part "DAC80502DRXT"))
    )
    (comp (ref "U903")
      (value "TS5A3159AYZPR")
      (footprint "TI_YZP6")
      (description "Analog Switch, SPDT, 2:1, DSBGA6")
      (fields (field (name "MANUFACTURER") "Texas Instruments"))
      (libsource (lib "MP-LIBRARY") (part "TS5A3159AYZPR"))
    )
    (comp (ref "U904")
      (value "TS5A3159AYZPR")
      (footprint "TI_YZP6")
      (description "Analog Switch, SPDT, 2:1, DSBGA6")
      (fields (field (name "MANUFACTURER") "Texas Instruments"))
      (libsource (lib "MP-LIBRARY") (part "TS5A3159AYZPR"))
    )
    (comp (ref "U905")
      (value "TLV9002SIYCKR")
      (footprint "TI_YCK0009")
      (description "Op Amp, Dual, Rail-to-Rail, 1MHz, BGA-9")
      (fields (field (name "MANUFACTURER") "Texas Instruments"))
      (libsource (lib "MP-LIBRARY") (part "TLV9002SIYCKR"))
    )
  )
  (nets
    (net (code "2") (name "/AMPL_RSTn") (class "Default")
      (node (ref "U900") (pin "3") (pinfunction "~{CLR}_3") (pintype "input"))
    )
    (net (code "3") (name "/B1") (class "Default")
      (node (ref "Q900") (pin "2") (pinfunction "B2_2") (pintype "passive"))
      (node (ref "Q900") (pin "3") (pinfunction "C1_3") (pintype "passive"))
      (node (ref "Q900") (pin "5") (pinfunction "B1_5") (pintype "passive"))
      (node (ref "Q901") (pin "3") (pinfunction "C_3") (pintype "passive"))
      (node (ref "R900") (pin "2") (pinfunction "2_2") (pintype "passive"))
    )
    (net (code "4") (name "/B2") (class "Default")
      (node (ref "Q902") (pin "2") (pinfunction "B2_2") (pintype "passive"))
      (node (ref "Q902") (pin "3") (pinfunction "C1_3") (pintype "passive"))
      (node (ref "Q902") (pin "5") (pinfunction "B1_5") (pintype "passive"))
      (node (ref "Q903") (pin "3") (pinfunction "C_3") (pintype "passive"))
      (node (ref "R905") (pin "2") (pinfunction "2_2") (pintype "passive"))
    )
    (net (code "5") (name "/B3") (class "Default")
      (node (ref "Q904") (pin "2") (pinfunction "B2_2") (pintype "passive"))
      (node (ref "Q904") (pin "3") (pinfunction "C1_3") (pintype "passive"))
      (node (ref "Q904") (pin "5") (pinfunction "B1_5") (pintype "passive"))
      (node (ref "Q905") (pin "3") (pinfunction "C_3") (pintype "passive"))
      (node (ref "R913") (pin "2") (pinfunction "2_2") (pintype "passive"))
    )
    (net (code "6") (name "/B4") (class "Default")
      (node (ref "Q906") (pin "2") (pinfunction "B2_2") (pintype "passive"))
      (node (ref "Q906") (pin "3") (pinfunction "C1_3") (pintype "passive"))
      (node (ref "Q906") (pin "5") (pinfunction "B1_5") (pintype "passive"))
      (node (ref "Q908") (pin "3") (pinfunction "C_3") (pintype "passive"))
      (node (ref "R918") (pin "2") (pinfunction "2_2") (pintype "passive"))
    )
    (net (code "7") (name "/B5") (class "Default")
      (node (ref "Q911") (pin "2") (pinfunction "B2_2") (pintype "passive"))
      (node (ref "Q911") (pin "3") (pinfunction "C1_3") (pintype "passive"))
      (node (ref "Q911") (pin "5") (pinfunction "B1_5") (pintype "passive"))
      (node (ref "Q912") (pin "3") (pinfunction "C_3") (pintype "passive"))
      (node (ref "R932") (pin "2") (pinfunction "2_2") (pintype "passive"))
    )
    (net (code "8") (name "/B6") (class "Default")
      (node (ref "Q913") (pin "2") (pinfunction "B2_2") (pintype "passive"))
      (node (ref "Q913") (pin "3") (pinfunction "C1_3") (pintype "passive"))
      (node (ref "Q913") (pin "5") (pinfunction "B1_5") (pintype "passive"))
      (node (ref "Q914") (pin "3") (pinfunction "C_3") (pintype "passive"))
      (node (ref "R937") (pin "2") (pinfunction "2_2") (pintype "passive"))
    )
    (net (code "9") (name "/B7") (class "Default")
      (node (ref "Q915") (pin "2") (pinfunction "B2_2") (pintype "passive"))
      (node (ref "Q915") (pin "3") (pinfunction "C1_3") (pintype "passive"))
      (node (ref "Q915") (pin "5") (pinfunction "B1_5") (pintype "passive"))
      (node (ref "Q916") (pin "3") (pinfunction "C_3") (pintype "passive"))
      (node (ref "R942") (pin "2") (pinfunction "2_2") (pintype "passive"))
    )
    (net (code "10") (name "/B8") (class "Default")
      (node (ref "Q917") (pin "2") (pinfunction "B2_2") (pintype "passive"))
      (node (ref "Q917") (pin "3") (pinfunction "C1_3") (pintype "passive"))
      (node (ref "Q917") (pin "5") (pinfunction "B1_5") (pintype "passive"))
      (node (ref "Q918") (pin "3") (pinfunction "C_3") (pintype "passive"))
      (node (ref "R947") (pin "2") (pinfunction "2_2") (pintype "passive"))
    )
    (net (code "11") (name "/B17") (class "Default")
      (node (ref "Q907") (pin "2") (pinfunction "B2_2") (pintype "passive"))
      (node (ref "Q907") (pin "3") (pinfunction "C1_3") (pintype "passive"))
      (node (ref "Q907") (pin "5") (pinfunction "B1_5") (pintype "passive"))
      (node (ref "Q909") (pin "3") (pinfunction "C_3") (pintype "passive"))
      (node (ref "R921") (pin "2") (pinfunction "2_2") (pintype "passive"))
    )
    (net (code "12") (name "/DAC_VOUTA") (class "Default")
      (node (ref "U902") (pin "2") (pinfunction "VOUTA_2") (pintype "output"))
      (node (ref "U903") (pin "1") (pinfunction "NO_1") (pintype "passive"))
    )
    (net (code "13") (name "/DAC_VOUTB") (class "Default")
      (node (ref "U902") (pin "9") (pinfunction "VOUTB_9") (pintype "output"))
      (node (ref "U904") (pin "1") (pinfunction "NO_1") (pintype "passive"))
    )
    (net (code "14") (name "/ENCL") (class "Default")
      (node (ref "C907") (pin "2") (pinfunction "2_2") (pintype "passive"))
    )
    (net (code "15") (name "/I2C2.SCL") (class "Default")
      (node (ref "U902") (pin "6") (pinfunction "SCLK_/_SCL_6") (pintype "input"))
    )
    (net (code "16") (name "/I2C2.SDA") (class "Default")
      (node (ref "U902") (pin "8") (pinfunction "SDIN_/_SDA_8") (pintype "input"))
    )
    (net (code "17") (name "/IMP1") (class "Default")
      (node (ref "R903") (pin "2") (pinfunction "2_2") (pintype "passive"))
      (node (ref "R904") (pin "1") (pinfunction "1_1") (pintype "passive"))
    )
    (net (code "18") (name "/IMP2") (class "Default")
      (node (ref "R910") (pin "2") (pinfunction "2_2") (pintype "passive"))
      (node (ref "R911") (pin "1") (pinfunction "1_1") (pintype "passive"))
    )
    (net (code "19") (name "/IMP3") (class "Default")
      (node (ref "R916") (pin "2") (pinfunction "2_2") (pintype "passive"))
      (node (ref "R917") (pin "1") (pinfunction "1_1") (pintype "passive"))
    )
    (net (code "20") (name "/IMP4") (class "Default")
      (node (ref "R924") (pin "2") (pinfunction "2_2") (pintype "passive"))
      (node (ref "R926") (pin "1") (pinfunction "1_1") (pintype "passive"))
    )
    (net (code "21") (name "/IMP5") (class "Default")
      (node (ref "R935") (pin "2") (pinfunction "2_2") (pintype "passive"))
      (node (ref "R936") (pin "1") (pinfunction "1_1") (pintype "passive"))
    )
    (net (code "22") (name "/IMP6") (class "Default")
      (node (ref "R940") (pin "2") (pinfunction "2_2") (pintype "passive"))
      (node (ref "R941") (pin "1") (pinfunction "1_1") (pintype "passive"))
    )
    (net (code "23") (name "/IMP7") (class "Default")
      (node (ref "R945") (pin "2") (pinfunction "2_2") (pintype "passive"))
      (node (ref "R946") (pin "1") (pinfunction "1_1") (pintype "passive"))
    )
    (net (code "24") (name "/IMP8") (class "Default")
      (node (ref "R950") (pin "2") (pinfunction "2_2") (pintype "passive"))
      (node (ref "R951") (pin "1") (pinfunction "1_1") (pintype "passive"))
    )
    (net (code "25") (name "/IMP17") (class "Default")
      (node (ref "R925") (pin "2") (pinfunction "2_2") (pintype "passive"))
      (node (ref "R927") (pin "1") (pinfunction "1_1") (pintype "passive"))
    )
    (net (code "27") (name "/IREF") (class "Default")
      (node (ref "Q901") (pin "2") (pinfunction "E_2") (pintype "passive"))
      (node (ref "Q903") (pin "2") (pinfunction "E_2") (pintype "passive"))
      (node (ref "Q905") (pin "2") (pinfunction "E_2") (pintype "passive"))
      (node (ref "Q908") (pin "2") (pinfunction "E_2") (pintype "passive"))
      (node (ref "Q909") (pin "2") (pinfunction "E_2") (pintype "passive"))
      (node (ref "Q910") (pin "3") (pinfunction "C_3") (pintype "passive"))
      (node (ref "Q912") (pin "2") (pinfunction "E_2") (pintype "passive"))
      (node (ref "Q914") (pin "2") (pinfunction "E_2") (pintype "passive"))
      (node (ref "Q916") (pin "2") (pinfunction "E_2") (pintype "passive"))
      (node (ref "Q918") (pin "2") (pinfunction "E_2") (pintype "passive"))
    )
    (net (code "28") (name "/PG_START") (class "Default")
      (node (ref "U900") (pin "2") (pinfunction "B_2") (pintype "input"))
    )
    (net (code "29") (name "/PH1_EN") (class "Default")
      (node (ref "U901") (pin "1") (pinfunction "1A_1") (pintype "input"))
    )
    (net (code "30") (name "/PH1_OUT") (class "Default")
      (node (ref "TP900") (pin "1") (pinfunction "1_1") (pintype "passive"))
      (node (ref "U901") (pin "7") (pinfunction "1Y_7") (pintype "output"))
      (node (ref "U903") (pin "6") (pinfunction "IN_6") (pintype "input"))
    )
    (net (code "31") (name "/PH2_EN") (class "Default")
      (node (ref "U901") (pin "6") (pinfunction "2B_6") (pintype "input"))
    )
    (net (code "32") (name "/PH2_OUT") (class "Default")
      (node (ref "TP901") (pin "1") (pinfunction "1_1") (pintype "passive"))
      (node (ref "U901") (pin "3") (pinfunction "2Y_3") (pintype "output"))
      (node (ref "U904") (pin "6") (pinfunction "IN_6") (pintype "input"))
    )
    (net (code "33") (name "/SNK1") (class "Default")
      (node (ref "M900") (pin "1") (pinfunction "G_1") (pintype "passive"))
    )
    (net (code "34") (name "/SNK2") (class "Default")
      (node (ref "M901") (pin "1") (pinfunction "G_1") (pintype "passive"))
    )
    (net (code "35") (name "/SNK3") (class "Default")
      (node (ref "M902") (pin "1") (pinfunction "G_1") (pintype "passive"))
    )
    (net (code "36") (name "/SNK4") (class "Default")
      (node (ref "M903") (pin "1") (pinfunction "G_1") (pintype "passive"))
    )
    (net (code "37") (name "/SNK5") (class "Default")
      (node (ref "M905") (pin "1") (pinfunction "G_1") (pintype "passive"))
    )
    (net (code "38") (name "/SNK6") (class "Default")
      (node (ref "M906") (pin "1") (pinfunction "G_1") (pintype "passive"))
    )
    (net (code "39") (name "/SNK7") (class "Default")
      (node (ref "M907") (pin "1") (pinfunction "G_1") (pintype "passive"))
    )
    (net (code "40") (name "/SNK8") (class "Default")
      (node (ref "M908") (pin "1") (pinfunction "G_1") (pintype "passive"))
    )
    (net (code "41") (name "/SNK17") (class "Default")
      (node (ref "M904") (pin "1") (pinfunction "G_1") (pintype "passive"))
    )
    (net (code "43") (name "/SNS_STIM1") (class "Default")
      (node (ref "C900") (pin "2") (pinfunction "2_2") (pintype "passive"))
    )
    (net (code "44") (name "/SNS_STIM2") (class "Default")
      (node (ref "C902") (pin "2") (pinfunction "2_2") (pintype "passive"))
    )
    (net (code "45") (name "/SNS_STIM3") (class "Default")
      (node (ref "C904") (pin "2") (pinfunction "2_2") (pintype "passive"))
    )
    (net (code "46") (name "/SNS_STIM4") (class "Default")
      (node (ref "C906") (pin "2") (pinfunction "2_2") (pintype "passive"))
    )
    (net (code "48") (name "/SRC1") (class "Default")
      (node (ref "Q901") (pin "1") (pinfunction "B_1") (pintype "passive"))
    )
    (net (code "49") (name "/SRC2") (class "Default")
      (node (ref "Q903") (pin "1") (pinfunction "B_1") (pintype "passive"))
    )
    (net (code "50") (name "/SRC3") (class "Default")
      (node (ref "Q905") (pin "1") (pinfunction "B_1") (pintype "passive"))
    )
    (net (code "51") (name "/SRC4") (class "Default")
      (node (ref "Q908") (pin "1") (pinfunction "B_1") (pintype "passive"))
    )
    (net (code "52") (name "/SRC5") (class "Default")
      (node (ref "Q912") (pin "1") (pinfunction "B_1") (pintype "passive"))
    )
    (net (code "53") (name "/SRC6") (class "Default")
      (node (ref "Q914") (pin "1") (pinfunction "B_1") (pintype "passive"))
    )
    (net (code "54") (name "/SRC7") (class "Default")
      (node (ref "Q916") (pin "1") (pinfunction "B_1") (pintype "passive"))
    )
    (net (code "55") (name "/SRC8") (class "Default")
      (node (ref "Q918") (pin "1") (pinfunction "B_1") (pintype "passive"))
    )
    (net (code "56") (name "/SRC17") (class "Default")
      (node (ref "Q909") (pin "1") (pinfunction "B_1") (pintype "passive"))
    )
    (net (code "58") (name "/STIM_EN") (class "Default")
      (node (ref "U905") (pin "B2") (pinfunction "~{SHDN}_B2") (pintype "input"))
    )
    (net (code "59") (name "/VDAC") (class "Default")
      (node (ref "R929") (pin "1") (pinfunction "1_1") (pintype "passive"))
      (node (ref "U903") (pin "4") (pinfunction "COM_4") (pintype "passive"))
      (node (ref "U904") (pin "4") (pinfunction "COM_4") (pintype "passive"))
      (node (ref "U905") (pin "A1") (pinfunction "IN1+_A1") (pintype "passive"))
    )
    (net (code "60") (name "/VDAC_BUF") (class "Default")
      (node (ref "Q910") (pin "2") (pinfunction "E_2") (pintype "passive"))
      (node (ref "R930") (pin "2") (pinfunction "2_2") (pintype "passive"))
      (node (ref "U905") (pin "B1") (pinfunction "IN1-_B1") (pintype "passive"))
    )
    (net (code "61") (name "/VNS_STIM5") (class "Default")
      (node (ref "C909") (pin "2") (pinfunction "2_2") (pintype "passive"))
    )
    (net (code "62") (name "/VNS_STIM6") (class "Default")
      (node (ref "C910") (pin "2") (pinfunction "2_2") (pintype "passive"))
    )
    (net (code "63") (name "/VNS_STIM7") (class "Default")
      (node (ref "C911") (pin "2") (pinfunction "2_2") (pintype "passive"))
    )
    (net (code "64") (name "/VNS_STIM8") (class "Default")
      (node (ref "C912") (pin "2") (pinfunction "2_2") (pintype "passive"))
    )
    (net (code "67") (name "GND") (class "Default")
      (node (ref "C901") (pin "1") (pinfunction "1_1") (pintype "passive"))
      (node (ref "C905") (pin "1") (pinfunction "1_1") (pintype "passive"))
      (node (ref "C908") (pin "1") (pinfunction "1_1") (pintype "passive"))
      (node (ref "M900") (pin "2") (pinfunction "S_2") (pintype "passive"))
      (node (ref "M901") (pin "2") (pinfunction "S_2") (pintype "passive"))
      (node (ref "M902") (pin "2") (pinfunction "S_2") (pintype "passive"))
      (node (ref "M903") (pin "2") (pinfunction "S_2") (pintype "passive"))
      (node (ref "M904") (pin "2") (pinfunction "S_2") (pintype "passive"))
      (node (ref "M905") (pin "2") (pinfunction "S_2") (pintype "passive"))
      (node (ref "M906") (pin "2") (pinfunction "S_2") (pintype "passive"))
      (node (ref "M907") (pin "2") (pinfunction "S_2") (pintype "passive"))
      (node (ref "M908") (pin "2") (pinfunction "S_2") (pintype "passive"))
      (node (ref "R904") (pin "2") (pinfunction "2_2") (pintype "passive"))
      (node (ref "R911") (pin "2") (pinfunction "2_2") (pintype "passive"))
      (node (ref "R917") (pin "2") (pinfunction "2_2") (pintype "passive"))
      (node (ref "R926") (pin "2") (pinfunction "2_2") (pintype "passive"))
      (node (ref "R927") (pin "2") (pinfunction "2_2") (pintype "passive"))
      (node (ref "R929") (pin "2") (pinfunction "2_2") (pintype "passive"))
      (node (ref "R930") (pin "1") (pinfunction "1_1") (pintype "passive"))
      (node (ref "R931") (pin "2") (pinfunction "2_2") (pintype "passive"))
      (node (ref "R936") (pin "2") (pinfunction "2_2") (pintype "passive"))
      (node (ref "R941") (pin "2") (pinfunction "2_2") (pintype "passive"))
      (node (ref "R946") (pin "2") (pinfunction "2_2") (pintype "passive"))
      (node (ref "R951") (pin "2") (pinfunction "2_2") (pintype "passive"))
      (node (ref "U900") (pin "1") (pinfunction "~{A}_1") (pintype "input"))
      (node (ref "U900") (pin "4") (pinfunction "GND_4") (pintype "power_in"))
      (node (ref "U901") (pin "4") (pinfunction "GND_4") (pintype "power_in"))
      (node (ref "U902") (pin "3") (pinfunction "RSTSEL_3") (pintype "input"))
      (node (ref "U902") (pin "4") (pinfunction "AGND_4") (pintype "power_in"))
      (node (ref "U902") (pin "7") (pinfunction "~{SYNC}_/_A0_7") (pintype "input"))
      (node (ref "U903") (pin "2") (pinfunction "GND_2") (pintype "power_in"))
      (node (ref "U904") (pin "2") (pinfunction "GND_2") (pintype "power_in"))
      (node (ref "U905") (pin "A2") (pinfunction "V-_A2") (pintype "power_in"))
    )
    (net (code "68") (name "Net-(M900-D)") (class "Default")
      (node (ref "C900") (pin "1") (pinfunction "1_1") (pintype "passive"))
      (node (ref "M900") (pin "3") (pinfunction "D_3") (pintype "passive"))
      (node (ref "Q900") (pin "6") (pinfunction "C2_6") (pintype "passive"))
      (node (ref "R903") (pin "1") (pinfunction "1_1") (pintype "passive"))
    )
    (net (code "69") (name "Net-(M901-D)") (class "Default")
      (node (ref "C902") (pin "1") (pinfunction "1_1") (pintype "passive"))
      (node (ref "M901") (pin "3") (pinfunction "D_3") (pintype "passive"))
      (node (ref "Q902") (pin "6") (pinfunction "C2_6") (pintype "passive"))
      (node (ref "R910") (pin "1") (pinfunction "1_1") (pintype "passive"))
    )
    (net (code "70") (name "Net-(M902-D)") (class "Default")
      (node (ref "C904") (pin "1") (pinfunction "1_1") (pintype "passive"))
      (node (ref "M902") (pin "3") (pinfunction "D_3") (pintype "passive"))
      (node (ref "Q904") (pin "6") (pinfunction "C2_6") (pintype "passive"))
      (node (ref "R916") (pin "1") (pinfunction "1_1") (pintype "passive"))
    )
    (net (code "71") (name "Net-(M903-D)") (class "Default")
      (node (ref "C906") (pin "1") (pinfunction "1_1") (pintype "passive"))
      (node (ref "M903") (pin "3") (pinfunction "D_3") (pintype "passive"))
      (node (ref "Q906") (pin "6") (pinfunction "C2_6") (pintype "passive"))
      (node (ref "R924") (pin "1") (pinfunction "1_1") (pintype "passive"))
    )
    (net (code "72") (name "Net-(M904-D)") (class "Default")
      (node (ref "C907") (pin "1") (pinfunction "1_1") (pintype "passive"))
      (node (ref "M904") (pin "3") (pinfunction "D_3") (pintype "passive"))
      (node (ref "Q907") (pin "6") (pinfunction "C2_6") (pintype "passive"))
      (node (ref "R925") (pin "1") (pinfunction "1_1") (pintype "passive"))
    )
    (net (code "73") (name "Net-(M905-D)") (class "Default")
      (node (ref "C909") (pin "1") (pinfunction "1_1") (pintype "passive"))
      (node (ref "M905") (pin "3") (pinfunction "D_3") (pintype "passive"))
      (node (ref "Q911") (pin "6") (pinfunction "C2_6") (pintype "passive"))
      (node (ref "R935") (pin "1") (pinfunction "1_1") (pintype "passive"))
    )
    (net (code "74") (name "Net-(M906-D)") (class "Default")
      (node (ref "C910") (pin "1") (pinfunction "1_1") (pintype "passive"))
      (node (ref "M906") (pin "3") (pinfunction "D_3") (pintype "passive"))
      (node (ref "Q913") (pin "6") (pinfunction "C2_6") (pintype "passive"))
      (node (ref "R940") (pin "1") (pinfunction "1_1") (pintype "passive"))
    )
    (net (code "75") (name "Net-(M907-D)") (class "Default")
      (node (ref "C911") (pin "1") (pinfunction "1_1") (pintype "passive"))
      (node (ref "M907") (pin "3") (pinfunction "D_3") (pintype "passive"))
      (node (ref "Q915") (pin "6") (pinfunction "C2_6") (pintype "passive"))
      (node (ref "R945") (pin "1") (pinfunction "1_1") (pintype "passive"))
    )
    (net (code "76") (name "Net-(M908-D)") (class "Default")
      (node (ref "C912") (pin "1") (pinfunction "1_1") (pintype "passive"))
      (node (ref "M908") (pin "3") (pinfunction "D_3") (pintype "passive"))
      (node (ref "Q917") (pin "6") (pinfunction "C2_6") (pintype "passive"))
      (node (ref "R950") (pin "1") (pinfunction "1_1") (pintype "passive"))
    )
    (net (code "77") (name "Net-(Q900-E1)") (class "Default")
      (node (ref "Q900") (pin "4") (pinfunction "E1_4") (pintype "passive"))
      (node (ref "R901") (pin "2") (pinfunction "2_2") (pintype "passive"))
    )
    (net (code "78") (name "Net-(Q900-E2)") (class "Default")
      (node (ref "Q900") (pin "1") (pinfunction "E2_1") (pintype "passive"))
      (node (ref "R902") (pin "1") (pinfunction "1_1") (pintype "passive"))
    )
    (net (code "79") (name "Net-(Q902-E1)") (class "Default")
      (node (ref "Q902") (pin "4") (pinfunction "E1_4") (pintype "passive"))
      (node (ref "R906") (pin "2") (pinfunction "2_2") (pintype "passive"))
    )
    (net (code "80") (name "Net-(Q902-E2)") (class "Default")
      (node (ref "Q902") (pin "1") (pinfunction "E2_1") (pintype "passive"))
      (node (ref "R907") (pin "1") (pinfunction "1_1") (pintype "passive"))
    )
    (net (code "81") (name "Net-(Q904-E1)") (class "Default")
      (node (ref "Q904") (pin "4") (pinfunction "E1_4") (pintype "passive"))
      (node (ref "R914") (pin "2") (pinfunction "2_2") (pintype "passive"))
    )
    (net (code "82") (name "Net-(Q904-E2)") (class "Default")
      (node (ref "Q904") (pin "1") (pinfunction "E2_1") (pintype "passive"))
      (node (ref "R915") (pin "1") (pinfunction "1_1") (pintype "passive"))
    )
    (net (code "83") (name "Net-(Q906-E1)") (class "Default")
      (node (ref "Q906") (pin "4") (pinfunction "E1_4") (pintype "passive"))
      (node (ref "R919") (pin "2") (pinfunction "2_2") (pintype "passive"))
    )
    (net (code "84") (name "Net-(Q906-E2)") (class "Default")
      (node (ref "Q906") (pin "1") (pinfunction "E2_1") (pintype "passive"))
      (node (ref "R920") (pin "1") (pinfunction "1_1") (pintype "passive"))
    )
    (net (code "85") (name "Net-(Q907-E1)") (class "Default")
      (node (ref "Q907") (pin "4") (pinfunction "E1_4") (pintype "passive"))
      (node (ref "R922") (pin "2") (pinfunction "2_2") (pintype "passive"))
    )
    (net (code "86") (name "Net-(Q907-E2)") (class "Default")
      (node (ref "Q907") (pin "1") (pinfunction "E2_1") (pintype "passive"))
      (node (ref "R923") (pin "1") (pinfunction "1_1") (pintype "passive"))
    )
    (net (code "87") (name "Net-(Q910-B)") (class "Default")
      (node (ref "Q910") (pin "1") (pinfunction "B_1") (pintype "passive"))
      (node (ref "R928") (pin "2") (pinfunction "2_2") (pintype "passive"))
    )
    (net (code "88") (name "Net-(Q911-E1)") (class "Default")
      (node (ref "Q911") (pin "4") (pinfunction "E1_4") (pintype "passive"))
      (node (ref "R933") (pin "2") (pinfunction "2_2") (pintype "passive"))
    )
    (net (code "89") (name "Net-(Q911-E2)") (class "Default")
      (node (ref "Q911") (pin "1") (pinfunction "E2_1") (pintype "passive"))
      (node (ref "R934") (pin "1") (pinfunction "1_1") (pintype "passive"))
    )
    (net (code "90") (name "Net-(Q913-E1)") (class "Default")
      (node (ref "Q913") (pin "4") (pinfunction "E1_4") (pintype "passive"))
      (node (ref "R938") (pin "2") (pinfunction "2_2") (pintype "passive"))
    )
    (net (code "91") (name "Net-(Q913-E2)") (class "Default")
      (node (ref "Q913") (pin "1") (pinfunction "E2_1") (pintype "passive"))
      (node (ref "R939") (pin "1") (pinfunction "1_1") (pintype "passive"))
    )
    (net (code "92") (name "Net-(Q915-E1)") (class "Default")
      (node (ref "Q915") (pin "4") (pinfunction "E1_4") (pintype "passive"))
      (node (ref "R943") (pin "2") (pinfunction "2_2") (pintype "passive"))
    )
    (net (code "93") (name "Net-(Q915-E2)") (class "Default")
      (node (ref "Q915") (pin "1") (pinfunction "E2_1") (pintype "passive"))
      (node (ref "R944") (pin "1") (pinfunction "1_1") (pintype "passive"))
    )
    (net (code "94") (name "Net-(Q917-E1)") (class "Default")
      (node (ref "Q917") (pin "4") (pinfunction "E1_4") (pintype "passive"))
      (node (ref "R948") (pin "2") (pinfunction "2_2") (pintype "passive"))
    )
    (net (code "95") (name "Net-(Q917-E2)") (class "Default")
      (node (ref "Q917") (pin "1") (pinfunction "E2_1") (pintype "passive"))
      (node (ref "R949") (pin "1") (pinfunction "1_1") (pintype "passive"))
    )
    (net (code "96") (name "Net-(U900-CEXT)") (class "Default")
      (node (ref "C903") (pin "1") (pinfunction "1_1") (pintype "passive"))
      (node (ref "U900") (pin "6") (pinfunction "CEXT_6") (pintype "passive"))
    )
    (net (code "97") (name "Net-(U900-Q)") (class "Default")
      (node (ref "R912") (pin "1") (pinfunction "1_1") (pintype "passive"))
      (node (ref "U900") (pin "5") (pinfunction "Q_5") (pintype "output"))
    )
    (net (code "98") (name "Net-(U900-REXT_{slash}_CEXT)") (class "Default")
      (node (ref "C903") (pin "2") (pinfunction "2_2") (pintype "passive"))
      (node (ref "R908") (pin "2") (pinfunction "2_2") (pintype "passive"))
      (node (ref "U900") (pin "7") (pinfunction "REXT_/_CEXT_7") (pintype "passive"))
    )
    (net (code "99") (name "Net-(U901-1B)") (class "Default")
      (node (ref "R909") (pin "2") (pinfunction "2_2") (pintype "passive"))
      (node (ref "R912") (pin "2") (pinfunction "2_2") (pintype "passive"))
      (node (ref "U901") (pin "2") (pinfunction "1B_2") (pintype "input"))
      (node (ref "U901") (pin "5") (pinfunction "2A_5") (pintype "input"))
    )
    (net (code "100") (name "Net-(U902-VREFIO)") (class "Default")
      (node (ref "TP902") (pin "1") (pinfunction "1_1") (pintype "passive"))
      (node (ref "U902") (pin "10") (pinfunction "VREFIO_10") (pintype "power_in"))
    )
    (net (code "101") (name "Net-(U905-IN2+)") (class "Default")
      (node (ref "R931") (pin "1") (pinfunction "1_1") (pintype "passive"))
      (node (ref "U905") (pin "A3") (pinfunction "IN2+_A3") (pintype "passive"))
      (node (ref "U905") (pin "B3") (pinfunction "IN2-_B3") (pintype "passive"))
    )
    (net (code "102") (name "Net-(U905-OUT1)") (class "Default")
      (node (ref "R928") (pin "1") (pinfunction "1_1") (pintype "passive"))
      (node (ref "U905") (pin "C1") (pinfunction "OUT1_C1") (pintype "passive"))
    )
    (net (code "103") (name "VDDS") (class "Default")
      (node (ref "C901") (pin "2") (pinfunction "2_2") (pintype "passive"))
      (node (ref "C905") (pin "2") (pinfunction "2_2") (pintype "passive"))
      (node (ref "C908") (pin "2") (pinfunction "2_2") (pintype "passive"))
      (node (ref "R908") (pin "1") (pinfunction "1_1") (pintype "passive"))
      (node (ref "R909") (pin "1") (pinfunction "1_1") (pintype "passive"))
      (node (ref "U900") (pin "8") (pinfunction "VCC_8") (pintype "power_in"))
      (node (ref "U901") (pin "8") (pinfunction "VCC_8") (pintype "power_in"))
      (node (ref "U902") (pin "1") (pinfunction "VDD_1") (pintype "power_in"))
      (node (ref "U902") (pin "5") (pinfunction "SPI2C_5") (pintype "input"))
      (node (ref "U903") (pin "5") (pinfunction "V+_5") (pintype "power_in"))
      (node (ref "U904") (pin "5") (pinfunction "V+_5") (pintype "power_in"))
      (node (ref "U905") (pin "C2") (pinfunction "V+_C2") (pintype "power_in"))
    )
    (net (code "104") (name "VPP") (class "Default")
      (node (ref "R900") (pin "1") (pinfunction "1_1") (pintype "passive"))
      (node (ref "R901") (pin "1") (pinfunction "1_1") (pintype "passive"))
      (node (ref "R902") (pin "2") (pinfunction "2_2") (pintype "passive"))
      (node (ref "R905") (pin "1") (pinfunction "1_1") (pintype "passive"))
      (node (ref "R906") (pin "1") (pinfunction "1_1") (pintype "passive"))
      (node (ref "R907") (pin "2") (pinfunction "2_2") (pintype "passive"))
      (node (ref "R913") (pin "1") (pinfunction "1_1") (pintype "passive"))
      (node (ref "R914") (pin "1") (pinfunction "1_1") (pintype "passive"))
      (node (ref "R915") (pin "2") (pinfunction "2_2") (pintype "passive"))
      (node (ref "R918") (pin "1") (pinfunction "1_1") (pintype "passive"))
      (node (ref "R919") (pin "1") (pinfunction "1_1") (pintype "passive"))
      (node (ref "R920") (pin "2") (pinfunction "2_2") (pintype "passive"))
      (node (ref "R921") (pin "1") (pinfunction "1_1") (pintype "passive"))
      (node (ref "R922") (pin "1") (pinfunction "1_1") (pintype "passive"))
      (node (ref "R923") (pin "2") (pinfunction "2_2") (pintype "passive"))
      (node (ref "R932") (pin "1") (pinfunction "1_1") (pintype "passive"))
      (node (ref "R933") (pin "1") (pinfunction "1_1") (pintype "passive"))
      (node (ref "R934") (pin "2") (pinfunction "2_2") (pintype "passive"))
      (node (ref "R937") (pin "1") (pinfunction "1_1") (pintype "passive"))
      (node (ref "R938") (pin "1") (pinfunction "1_1") (pintype "passive"))
      (node (ref "R939") (pin "2") (pinfunction "2_2") (pintype "passive"))
      (node (ref "R942") (pin "1") (pinfunction "1_1") (pintype "passive"))
      (node (ref "R943") (pin "1") (pinfunction "1_1") (pintype "passive"))
      (node (ref "R944") (pin "2") (pinfunction "2_2") (pintype "passive"))
      (node (ref "R947") (pin "1") (pinfunction "1_1") (pintype "passive"))
      (node (ref "R948") (pin "1") (pinfunction "1_1") (pintype "passive"))
      (node (ref "R949") (pin "2") (pinfunction "2_2") (pintype "passive"))
    )
    (net (code "105") (name "unconnected-(U903-NC-Pad3)") (class "Default")
      (node (ref "U903") (pin "3") (pinfunction "NC_3") (pintype "passive+no_connect"))
    )
    (net (code "106") (name "unconnected-(U904-NC-Pad3)") (class "Default")
      (node (ref "U904") (pin "3") (pinfunction "NC_3") (pintype "passive+no_connect"))
    )
    (net (code "107") (name "unconnected-(U905-OUT2-PadC3)") (class "Default")
      (node (ref "U905") (pin "C3") (pinfunction "OUT2_C3") (pintype "passive+no_connect"))
    )
  )
)
